# BMS_Fan_Kill_Switch.net
KiCad netlist of a schematic drawn in Altium Designer
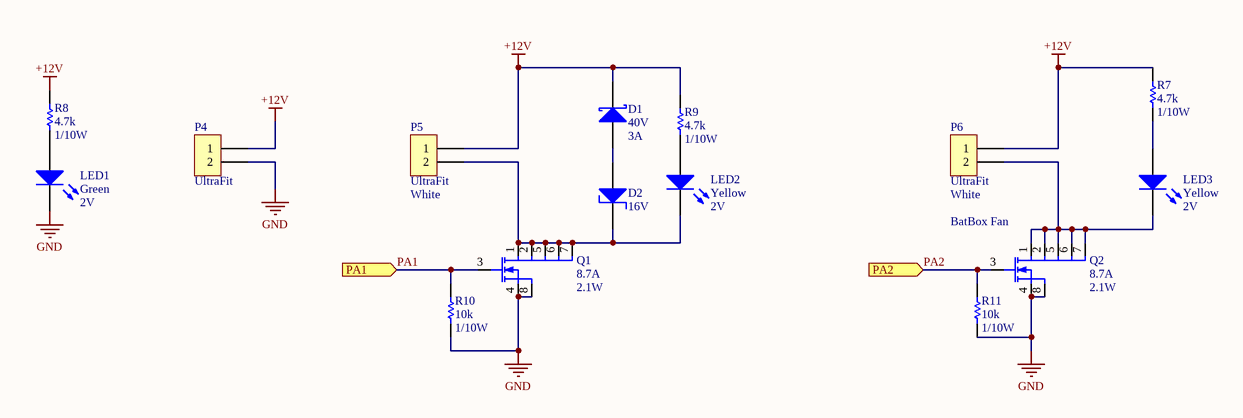
[diagram p0: BMS_Fan&Kill_Switch.SchDoc]

(export (version "E")
  (design (tool "Eeschema 10.0.6"))
  (components
    (comp (ref "D1")
      (value "DIODE SCHOTTKY 40V 3A DO-214AA (SMB)")
      (footprint "DO-214AA Diode")
      (description "Diode Schottky 40V 3A Surface Mount DO-214AA (SMB)")
      (fields
        (field (name "VOLTAGE - DC REVERSE (VR) (MAX)") "40V")
        (field (name "CURRENT - AVERAGE RECTIFIED (IO)") "3A")
      )
      (libsource (lib "Schematic Diagrams") (part "DIODE SCHOTTKY 40V 3A DO-214AA (SMB)"))
    )
    (comp (ref "D2")
      (value "DIODE ZENER 16V 5W DO-214AA (SMB)")
      (footprint "DO-214AA Diode")
      (description "Zener Diode 16V 5W ±5% Surface Mount DO-214AA (SMB)")
      (fields
        (field (name "MANUFACTURE PART NUMBER") "SMBJ5353B-TP")
        (field (name "VOLTAGE - ZENER (NOM)") "16V")
      )
      (libsource (lib "Schematic Diagrams") (part "DIODE ZENER 16V 5W DO-214AA (SMB)"))
    )
    (comp (ref "LED1")
      (value "LED GREEN CLEAR 2V 0603")
      (footprint "LED_0603")
      (description "Green 572nm LED Indication - Discrete 2V 0603 (1608 Metric)")
      (fields
        (field (name "MANUFACTURER") "Wurth Electronics Inc.")
        (field (name "MANUFACTURER PART NUMBER") "150060VS75000")
        (field (name "COLOR") "Green")
        (field (name "VOLTAGE - FORWARD (VF) (TYP)") "2V")
      )
      (libsource (lib "Schematic Diagrams") (part "LED GREEN CLEAR 2V 0603"))
    )
    (comp (ref "LED2")
      (value "LED YELLOW CLEAR 2.1V 0603")
      (footprint "LED_0603")
      (description "Yellow 590nm LED Indication - Discrete 2V 0603 (1608 Metric)")
      (fields
        (field (name "MANUFACTURER") "Wurth Electronics Inc.")
        (field (name "MANUFACTURER PART NUMBER") "150060YS75000")
        (field (name "COLOR") "Yellow")
        (field (name "VOLTAGE - FORWARD (VF) (TYP)") "2V")
      )
      (libsource (lib "Schematic Diagrams") (part "LED YELLOW CLEAR 2.1V 0603"))
    )
    (comp (ref "LED3")
      (value "LED YELLOW CLEAR 2.1V 0603")
      (footprint "LED_0603")
      (description "Yellow 590nm LED Indication - Discrete 2V 0603 (1608 Metric)")
      (fields
        (field (name "MANUFACTURER") "Wurth Electronics Inc.")
        (field (name "MANUFACTURER PART NUMBER") "150060YS75000")
        (field (name "COLOR") "Yellow")
        (field (name "VOLTAGE - FORWARD (VF) (TYP)") "2V")
      )
      (libsource (lib "Schematic Diagrams") (part "LED YELLOW CLEAR 2.1V 0603"))
    )
    (comp (ref "P4")
      (value "CONN 2POS ULTRA-FIT 0.138\"")
      (footprint "CONN, 2POS ULTRA-FIT")
      (description "2 Positions Header, Shrouded Connector 0.138\" (3.50mm) Through Hole Gold")
      (fields (field (name "VOLTAGE") "400V") (field (name "SERIES") "UltraFit"))
      (libsource (lib "Schematic Diagrams") (part "CONN 2POS ULTRA-FIT 0.138{dblquote}"))
    )
    (comp (ref "P5")
      (value "CONN 2POS ULTRA-FIT NATURAL COLOR 0.138\"")
      (footprint "CONN, 2POS ULTRA-FIT - NATURAL COLOR")
      (description "2 Positions Header, Shrouded Connector 0.138\" (3.50mm) Through Hole")
      (fields
        (field (name "VOLTAGE") "400V")
        (field (name "SERIES") "UltraFit")
        (field (name "COLOR") "White")
      )
      (libsource (lib "Schematic Diagrams") (part "CONN 2POS ULTRA-FIT NATURAL COLOR 0.138{dblquote}"))
    )
    (comp (ref "P6")
      (value "CONN 2POS ULTRA-FIT NATURAL COLOR 0.138\"")
      (footprint "CONN, 2POS ULTRA-FIT - NATURAL COLOR")
      (description "2 Positions Header, Shrouded Connector 0.138\" (3.50mm) Through Hole")
      (fields
        (field (name "VOLTAGE") "400V")
        (field (name "SERIES") "UltraFit")
        (field (name "COLOR") "White")
      )
      (libsource (lib "Schematic Diagrams") (part "CONN 2POS ULTRA-FIT NATURAL COLOR 0.138{dblquote}"))
    )
    (comp (ref "Q1")
      (value "MOSFET N-CH 30V 8.7A 2.1W 6-PQFN (2x2)")
      (footprint "MOSFET N-CH 30V 12A 2mmx2mm PQFN")
      (fields
        (field (name "CURRENT - CONTINUOUS DRAIN (ID) @ 25°C") "8.7A")
        (field (name "POWER DISSIPATION (MAX)") "2.1W")
      )
      (libsource (lib "Schematic Diagrams") (part "MOSFET N-CH 30V 8.7A 2.1W 6-PQFN (2x2)"))
    )
    (comp (ref "Q2")
      (value "MOSFET N-CH 30V 8.7A 2.1W 6-PQFN (2x2)")
      (footprint "MOSFET N-CH 30V 12A 2mmx2mm PQFN")
      (fields
        (field (name "CURRENT - CONTINUOUS DRAIN (ID) @ 25°C") "8.7A")
        (field (name "POWER DISSIPATION (MAX)") "2.1W")
      )
      (libsource (lib "Schematic Diagrams") (part "MOSFET N-CH 30V 8.7A 2.1W 6-PQFN (2x2)"))
    )
    (comp (ref "R7")
      (value "RES 4.7K OHM 1% 1/10W 0603")
      (footprint "RES, 0603")
      (description "4.7k Ohm ±1% 0.1W, 1/10W Chip Resistor 0603 (1608 Metric) Moisture Resistant Thick Film")
      (fields
        (field (name "TOLERANCE") "±1%")
        (field (name "RESISTANCE (OHMS)") "4.7k")
        (field (name "POWER (WATTS)") "1/10W")
      )
      (libsource (lib "Schematic Diagrams") (part "RES 4.7K OHM 1% 1/10W 0603"))
    )
    (comp (ref "R8")
      (value "RES 4.7K OHM 1% 1/10W 0603")
      (footprint "RES, 0603")
      (description "4.7k Ohm ±1% 0.1W, 1/10W Chip Resistor 0603 (1608 Metric) Moisture Resistant Thick Film")
      (fields
        (field (name "TOLERANCE") "±1%")
        (field (name "RESISTANCE (OHMS)") "4.7k")
        (field (name "POWER (WATTS)") "1/10W")
      )
      (libsource (lib "Schematic Diagrams") (part "RES 4.7K OHM 1% 1/10W 0603"))
    )
    (comp (ref "R9")
      (value "RES 4.7K OHM 1% 1/10W 0603")
      (footprint "RES, 0603")
      (description "4.7k Ohm ±1% 0.1W, 1/10W Chip Resistor 0603 (1608 Metric) Moisture Resistant Thick Film")
      (fields
        (field (name "TOLERANCE") "±1%")
        (field (name "RESISTANCE (OHMS)") "4.7k")
        (field (name "POWER (WATTS)") "1/10W")
      )
      (libsource (lib "Schematic Diagrams") (part "RES 4.7K OHM 1% 1/10W 0603"))
    )
    (comp (ref "R10")
      (value "RES 10K OHM 1% 1/10W 0603")
      (footprint "RES, 0603")
      (description "RES SMD 10K OHM 1% 1/10W 0603")
      (fields
        (field (name "TOLERANCE") "±1%")
        (field (name "RESISTANCE") "10k")
        (field (name "POWER") "1/10W")
      )
      (libsource (lib "Schematic Diagrams") (part "RES 10K OHM 1% 1/10W 0603"))
    )
    (comp (ref "R11")
      (value "RES 10K OHM 1% 1/10W 0603")
      (footprint "RES, 0603")
      (description "RES SMD 10K OHM 1% 1/10W 0603")
      (fields
        (field (name "TOLERANCE") "±1%")
        (field (name "RESISTANCE") "10k")
        (field (name "POWER") "1/10W")
      )
      (libsource (lib "Schematic Diagrams") (part "RES 10K OHM 1% 1/10W 0603"))
    )
  )
  (nets
    (net (code "1") (name "+12V") (class "Default")
      (node (ref "D1") (pin "2") (pinfunction "K_2") (pintype "passive"))
      (node (ref "P4") (pin "1") (pinfunction "1_1") (pintype "passive"))
      (node (ref "P5") (pin "1") (pinfunction "1_1") (pintype "passive"))
      (node (ref "P6") (pin "1") (pinfunction "1_1") (pintype "passive"))
      (node (ref "R7") (pin "1") (pinfunction "1_1") (pintype "passive"))
      (node (ref "R8") (pin "1") (pinfunction "1_1") (pintype "passive"))
      (node (ref "R9") (pin "1") (pinfunction "1_1") (pintype "passive"))
    )
    (net (code "2") (name "/PA1") (class "Default")
      (node (ref "Q1") (pin "3") (pinfunction "G_3") (pintype "passive"))
      (node (ref "R10") (pin "1") (pinfunction "1_1") (pintype "passive"))
    )
    (net (code "3") (name "/PA2") (class "Default")
      (node (ref "Q2") (pin "3") (pinfunction "G_3") (pintype "passive"))
      (node (ref "R11") (pin "1") (pinfunction "1_1") (pintype "passive"))
    )
    (net (code "4") (name "GND") (class "Default")
      (node (ref "LED1") (pin "2") (pinfunction "K_2") (pintype "passive"))
      (node (ref "P4") (pin "2") (pinfunction "2_2") (pintype "passive"))
      (node (ref "Q1") (pin "4") (pinfunction "S_4") (pintype "passive"))
      (node (ref "Q1") (pin "8") (pinfunction "S_8") (pintype "passive"))
      (node (ref "Q2") (pin "4") (pinfunction "S_4") (pintype "passive"))
      (node (ref "Q2") (pin "8") (pinfunction "S_8") (pintype "passive"))
      (node (ref "R10") (pin "2") (pinfunction "2_2") (pintype "passive"))
      (node (ref "R11") (pin "2") (pinfunction "2_2") (pintype "passive"))
    )
    (net (code "5") (name "Net-(D1-A)") (class "Default")
      (node (ref "D1") (pin "1") (pinfunction "A_1") (pintype "passive"))
      (node (ref "D2") (pin "1") (pinfunction "A_1") (pintype "passive"))
    )
    (net (code "6") (name "Net-(D2-K)") (class "Default")
      (node (ref "D2") (pin "2") (pinfunction "K_2") (pintype "passive"))
      (node (ref "LED2") (pin "2") (pinfunction "K_2") (pintype "passive"))
      (node (ref "P5") (pin "2") (pinfunction "2_2") (pintype "passive"))
      (node (ref "Q1") (pin "1") (pinfunction "D_1") (pintype "passive"))
      (node (ref "Q1") (pin "2") (pinfunction "D_2") (pintype "passive"))
      (node (ref "Q1") (pin "5") (pinfunction "D_5") (pintype "passive"))
      (node (ref "Q1") (pin "6") (pinfunction "D_6") (pintype "passive"))
      (node (ref "Q1") (pin "7") (pinfunction "D_7") (pintype "passive"))
    )
    (net (code "7") (name "Net-(LED1-A)") (class "Default")
      (node (ref "LED1") (pin "1") (pinfunction "A_1") (pintype "passive"))
      (node (ref "R8") (pin "2") (pinfunction "2_2") (pintype "passive"))
    )
    (net (code "8") (name "Net-(LED2-A)") (class "Default")
      (node (ref "LED2") (pin "1") (pinfunction "A_1") (pintype "passive"))
      (node (ref "R9") (pin "2") (pinfunction "2_2") (pintype "passive"))
    )
    (net (code "9") (name "Net-(LED3-A)") (class "Default")
      (node (ref "LED3") (pin "1") (pinfunction "A_1") (pintype "passive"))
      (node (ref "R7") (pin "2") (pinfunction "2_2") (pintype "passive"))
    )
    (net (code "10") (name "Net-(LED3-K)") (class "Default")
      (node (ref "LED3") (pin "2") (pinfunction "K_2") (pintype "passive"))
      (node (ref "P6") (pin "2") (pinfunction "2_2") (pintype "passive"))
      (node (ref "Q2") (pin "1") (pinfunction "D_1") (pintype "passive"))
      (node (ref "Q2") (pin "2") (pinfunction "D_2") (pintype "passive"))
      (node (ref "Q2") (pin "5") (pinfunction "D_5") (pintype "passive"))
      (node (ref "Q2") (pin "6") (pinfunction "D_6") (pintype "passive"))
      (node (ref "Q2") (pin "7") (pinfunction "D_7") (pintype "passive"))
    )
  )
)
